# Sheet1.net
KiCad netlist of a schematic drawn in EasyEDA Pro
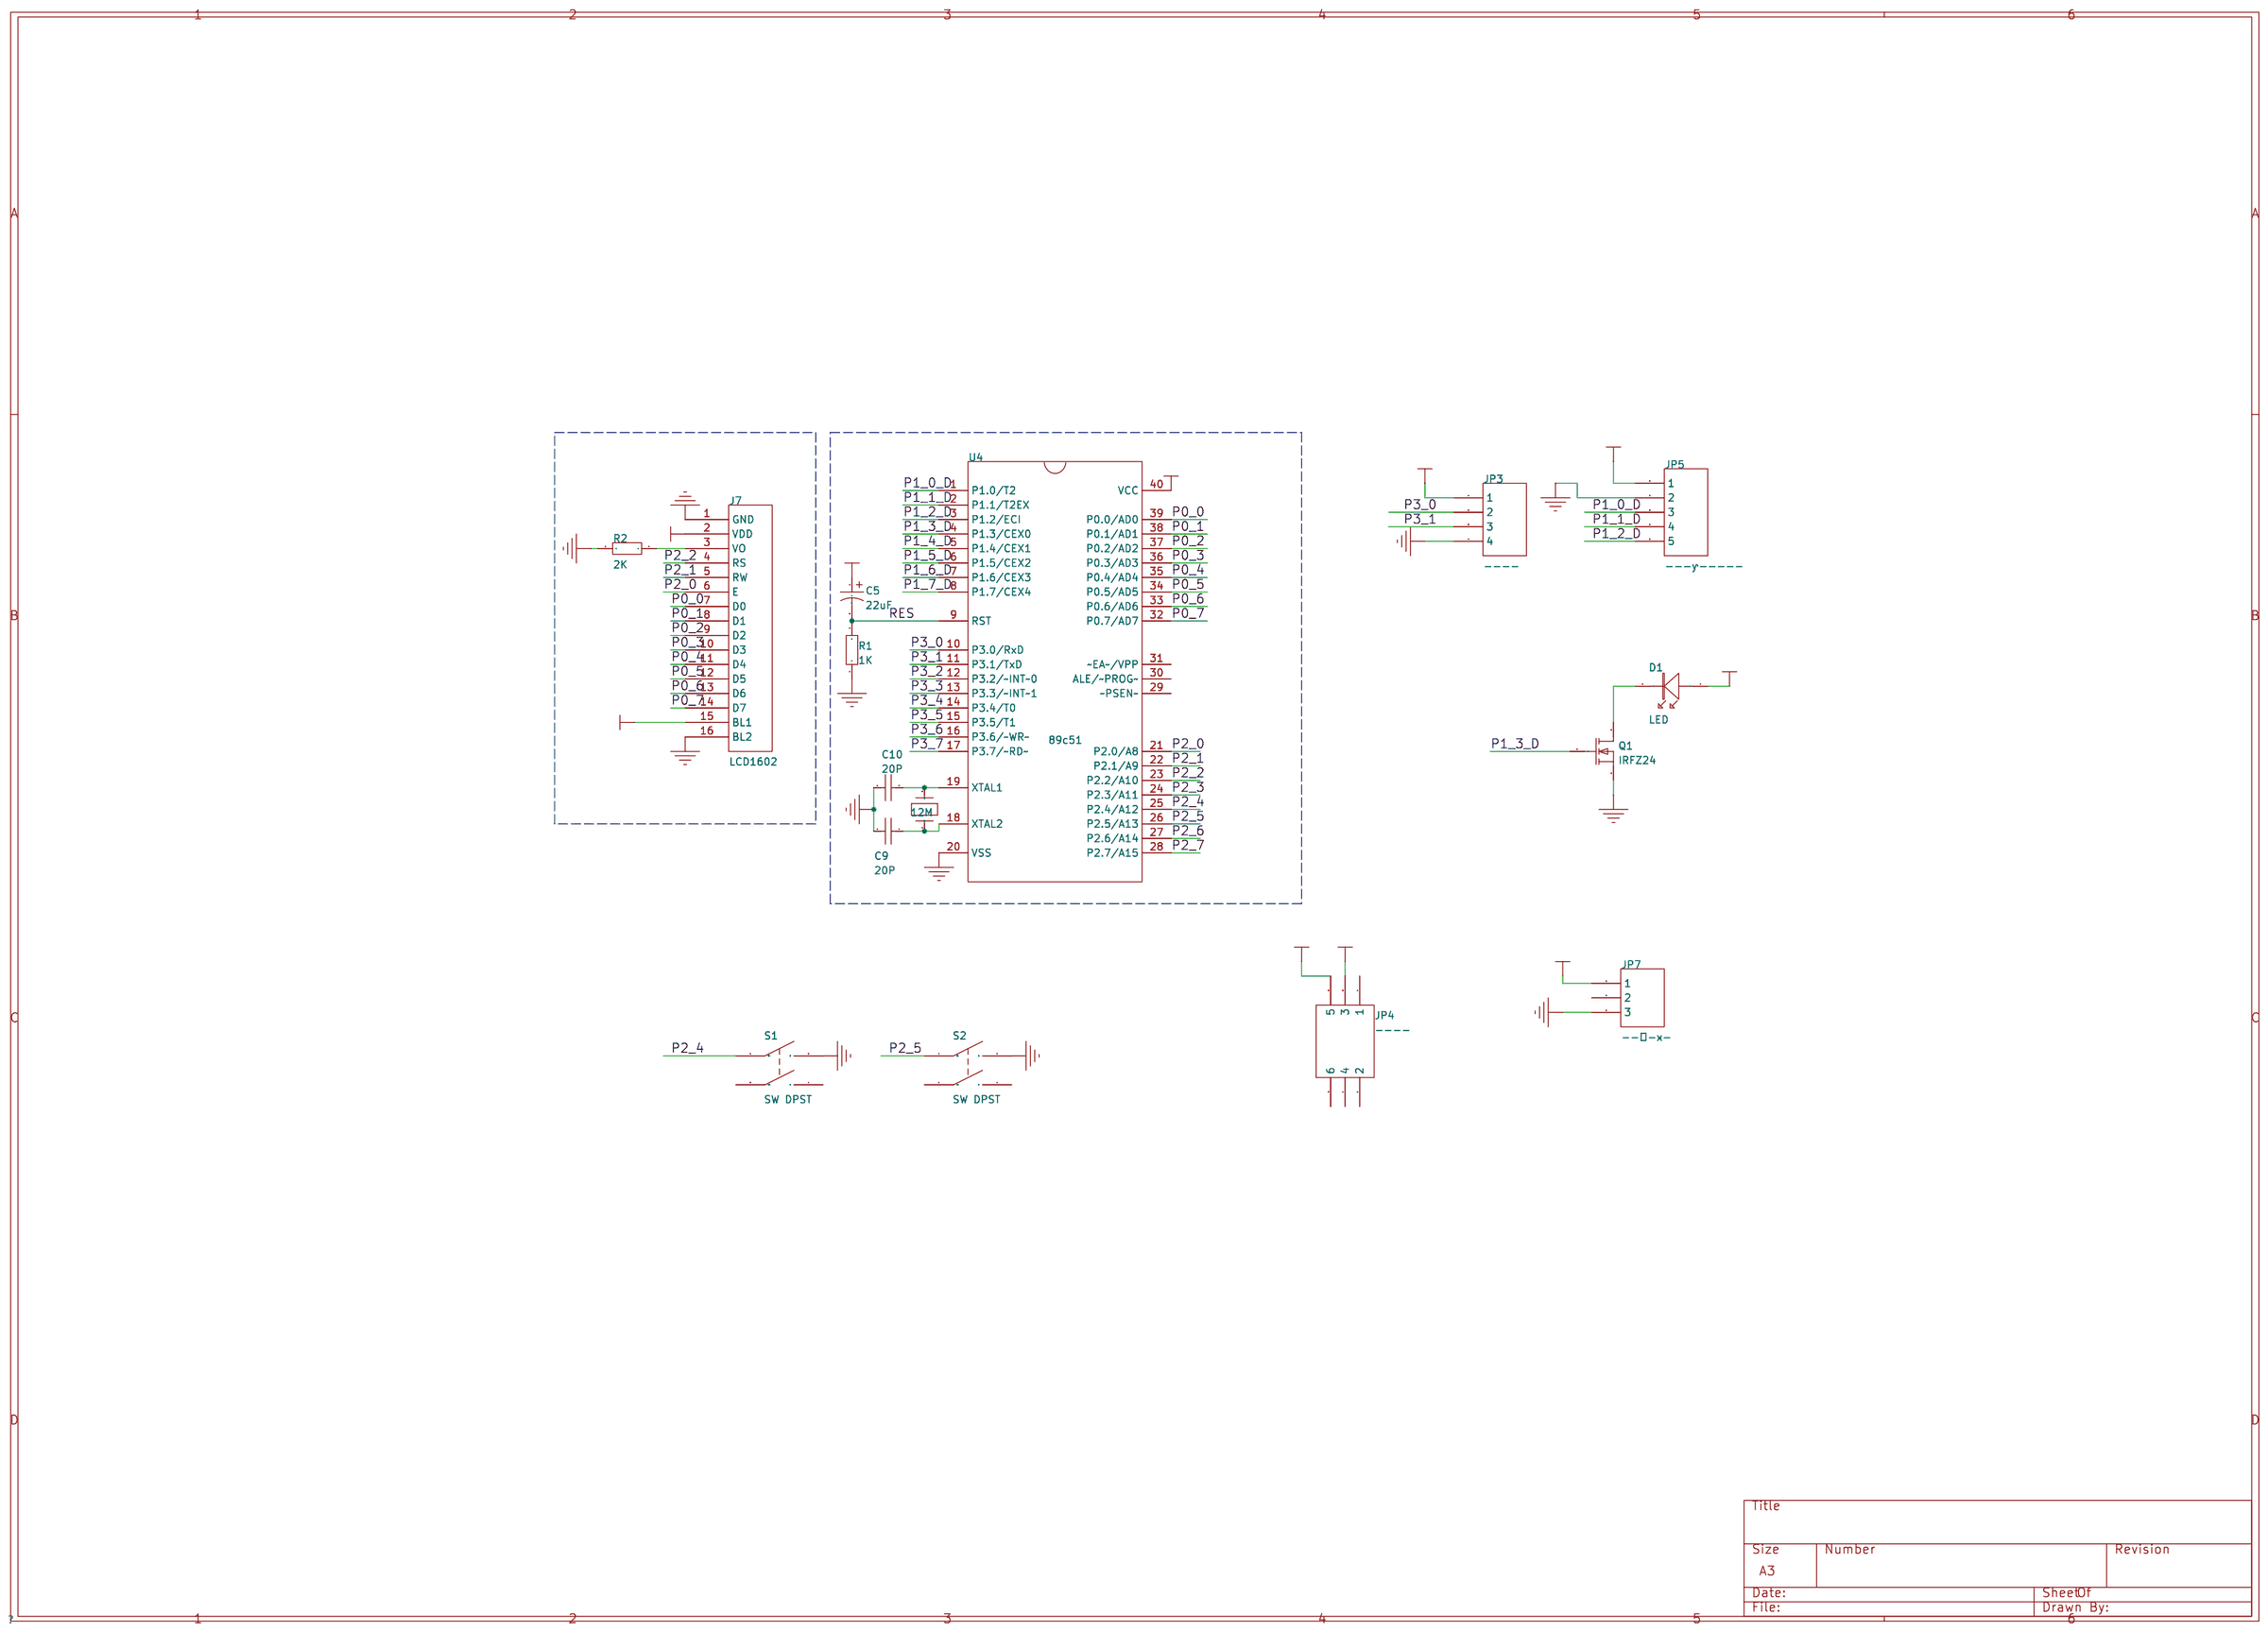
[diagram p0: schematic sheet]

(export (version "E")
  (design (tool "Eeschema 10.0.6"))
  (components
    (comp (ref "C5")
      (value "22uF")
      (description "Polarized Capacitor (Radial)")
      (fields (field (name "Publisher") "Altium Limited"))
      (libsource (lib "easyedapro") (part "Cap Pol1"))
    )
    (comp (ref "C9") (value "20P") (description "Capacitor") (libsource (lib "easyedapro") (part "CAP")))
    (comp (ref "C10") (value "20P") (description "Capacitor") (libsource (lib "easyedapro") (part "CAP")))
    (comp (ref "D1") (value "LED") (libsource (lib "easyedapro") (part "LED")))
    (comp (ref "J7") (value "LCD1602") (libsource (lib "easyedapro") (part "LCD1602")))
    (comp (ref "JP3")
      (value "----")
      (description "4 Pin Header")
      (libsource (lib "easyedapro") (part "4 HEADER"))
    )
    (comp (ref "JP4") (value "----") (libsource (lib "easyedapro") (part "HEADER 3X2")))
    (comp (ref "JP5") (value "---ƴ-----") (libsource (lib "easyedapro") (part "HEADER 5")))
    (comp (ref "JP7") (value "--Դ-ӿ-") (libsource (lib "easyedapro") (part "HEADER 3")))
    (comp (ref "Q1")
      (value "IRFZ24")
      (description "N-Channel MOSFET")
      (libsource (lib "easyedapro") (part "IRFZ24"))
    )
    (comp (ref "R1")
      (value "1K")
      (description "Resistor")
      (fields (field (name "Publisher") "Altium Limited"))
      (libsource (lib "easyedapro") (part "Res2"))
    )
    (comp (ref "R2")
      (value "2K")
      (description "Resistor")
      (fields (field (name "Publisher") "Altium Limited"))
      (libsource (lib "easyedapro") (part "Res2"))
    )
    (comp (ref "S1") (value "SW DPST") (libsource (lib "easyedapro") (part "SW DPST")))
    (comp (ref "S2") (value "SW DPST") (libsource (lib "easyedapro") (part "SW DPST")))
    (comp (ref "U4") (value "89c51") (libsource (lib "easyedapro") (part "89c51")))
    (comp (ref "Y4") (value "12M") (description "Crystal") (libsource (lib "easyedapro") (part "CRYSTAL")))
  )
  (nets
    (net (code "1") (name "/P0_0") (class "Default")
      (node (ref "J7") (pin "7") (pinfunction "D0_7") (pintype "unspecified"))
      (node (ref "U4") (pin "39") (pinfunction "P0.0/AD0_39") (pintype "bidirectional"))
    )
    (net (code "2") (name "/P0_1") (class "Default")
      (node (ref "J7") (pin "8") (pinfunction "D1_8") (pintype "unspecified"))
      (node (ref "U4") (pin "38") (pinfunction "P0.1/AD1_38") (pintype "bidirectional"))
    )
    (net (code "3") (name "/P0_2") (class "Default")
      (node (ref "J7") (pin "9") (pinfunction "D2_9") (pintype "unspecified"))
      (node (ref "U4") (pin "37") (pinfunction "P0.2/AD2_37") (pintype "bidirectional"))
    )
    (net (code "4") (name "/P0_3") (class "Default")
      (node (ref "J7") (pin "10") (pinfunction "D3_10") (pintype "unspecified"))
      (node (ref "U4") (pin "36") (pinfunction "P0.3/AD3_36") (pintype "bidirectional"))
    )
    (net (code "5") (name "/P0_4") (class "Default")
      (node (ref "J7") (pin "11") (pinfunction "D4_11") (pintype "unspecified"))
      (node (ref "U4") (pin "35") (pinfunction "P0.4/AD4_35") (pintype "bidirectional"))
    )
    (net (code "6") (name "/P0_5") (class "Default")
      (node (ref "J7") (pin "12") (pinfunction "D5_12") (pintype "unspecified"))
      (node (ref "U4") (pin "34") (pinfunction "P0.5/AD5_34") (pintype "bidirectional"))
    )
    (net (code "7") (name "/P0_6") (class "Default")
      (node (ref "J7") (pin "13") (pinfunction "D6_13") (pintype "unspecified"))
      (node (ref "U4") (pin "33") (pinfunction "P0.6/AD6_33") (pintype "bidirectional"))
    )
    (net (code "8") (name "/P0_7") (class "Default")
      (node (ref "J7") (pin "14") (pinfunction "D7_14") (pintype "unspecified"))
      (node (ref "U4") (pin "32") (pinfunction "P0.7/AD7_32") (pintype "bidirectional"))
    )
    (net (code "9") (name "/P1_0_D") (class "Default")
      (node (ref "JP5") (pin "3") (pinfunction "3_3") (pintype "unspecified"))
      (node (ref "U4") (pin "1") (pinfunction "P1.0/T2_1") (pintype "bidirectional"))
    )
    (net (code "10") (name "/P1_1_D") (class "Default")
      (node (ref "JP5") (pin "4") (pinfunction "4_4") (pintype "unspecified"))
      (node (ref "U4") (pin "2") (pinfunction "P1.1/T2EX_2") (pintype "bidirectional"))
    )
    (net (code "11") (name "/P1_2_D") (class "Default")
      (node (ref "JP5") (pin "5") (pinfunction "5_5") (pintype "unspecified"))
      (node (ref "U4") (pin "3") (pinfunction "P1.2/ECI_3") (pintype "bidirectional"))
    )
    (net (code "12") (name "/P1_3_D") (class "Default")
      (node (ref "Q1") (pin "1") (pinfunction "G_1") (pintype "input"))
      (node (ref "U4") (pin "4") (pinfunction "P1.3/CEX0_4") (pintype "bidirectional"))
    )
    (net (code "13") (name "/P1_4_D") (class "Default")
      (node (ref "U4") (pin "5") (pinfunction "P1.4/CEX1_5") (pintype "bidirectional"))
    )
    (net (code "14") (name "/P1_5_D") (class "Default")
      (node (ref "U4") (pin "6") (pinfunction "P1.5/CEX2_6") (pintype "bidirectional"))
    )
    (net (code "15") (name "/P1_6_D") (class "Default")
      (node (ref "U4") (pin "7") (pinfunction "P1.6/CEX3_7") (pintype "bidirectional"))
    )
    (net (code "16") (name "/P1_7_D") (class "Default")
      (node (ref "U4") (pin "8") (pinfunction "P1.7/CEX4_8") (pintype "bidirectional"))
    )
    (net (code "17") (name "/P2_0") (class "Default")
      (node (ref "J7") (pin "6") (pinfunction "E_6") (pintype "unspecified"))
      (node (ref "U4") (pin "21") (pinfunction "P2.0/A8_21") (pintype "bidirectional"))
    )
    (net (code "18") (name "/P2_1") (class "Default")
      (node (ref "J7") (pin "5") (pinfunction "RW_5") (pintype "unspecified"))
      (node (ref "U4") (pin "22") (pinfunction "P2.1/A9_22") (pintype "bidirectional"))
    )
    (net (code "19") (name "/P2_2") (class "Default")
      (node (ref "J7") (pin "4") (pinfunction "RS_4") (pintype "unspecified"))
      (node (ref "U4") (pin "23") (pinfunction "P2.2/A10_23") (pintype "bidirectional"))
    )
    (net (code "20") (name "/P2_3") (class "Default")
      (node (ref "U4") (pin "24") (pinfunction "P2.3/A11_24") (pintype "bidirectional"))
    )
    (net (code "21") (name "/P2_4") (class "Default")
      (node (ref "S1") (pin "1") (pinfunction "COMMON1_1") (pintype "unspecified"))
      (node (ref "U4") (pin "25") (pinfunction "P2.4/A12_25") (pintype "bidirectional"))
    )
    (net (code "22") (name "/P2_5") (class "Default")
      (node (ref "S2") (pin "1") (pinfunction "COMMON1_1") (pintype "unspecified"))
      (node (ref "U4") (pin "26") (pinfunction "P2.5/A13_26") (pintype "bidirectional"))
    )
    (net (code "23") (name "/P2_6") (class "Default")
      (node (ref "U4") (pin "27") (pinfunction "P2.6/A14_27") (pintype "bidirectional"))
    )
    (net (code "24") (name "/P2_7") (class "Default")
      (node (ref "U4") (pin "28") (pinfunction "P2.7/A15_28") (pintype "bidirectional"))
    )
    (net (code "25") (name "/P3_0") (class "Default")
      (node (ref "JP3") (pin "2") (pinfunction "2_2") (pintype "unspecified"))
      (node (ref "U4") (pin "10") (pinfunction "P3.0/RxD_10") (pintype "bidirectional"))
    )
    (net (code "26") (name "/P3_1") (class "Default")
      (node (ref "JP3") (pin "3") (pinfunction "3_3") (pintype "unspecified"))
      (node (ref "U4") (pin "11") (pinfunction "P3.1/TxD_11") (pintype "bidirectional"))
    )
    (net (code "27") (name "/P3_2") (class "Default")
      (node (ref "U4") (pin "12") (pinfunction "P3.2/~INT~0_12") (pintype "bidirectional"))
    )
    (net (code "28") (name "/P3_3") (class "Default")
      (node (ref "U4") (pin "13") (pinfunction "P3.3/~INT~1_13") (pintype "bidirectional"))
    )
    (net (code "29") (name "/P3_4") (class "Default")
      (node (ref "U4") (pin "14") (pinfunction "P3.4/T0_14") (pintype "bidirectional"))
    )
    (net (code "30") (name "/P3_5") (class "Default")
      (node (ref "U4") (pin "15") (pinfunction "P3.5/T1_15") (pintype "bidirectional"))
    )
    (net (code "31") (name "/P3_6") (class "Default")
      (node (ref "U4") (pin "16") (pinfunction "P3.6/~WR~_16") (pintype "bidirectional"))
    )
    (net (code "32") (name "/P3_7") (class "Default")
      (node (ref "U4") (pin "17") (pinfunction "P3.7/~RD~_17") (pintype "bidirectional"))
    )
    (net (code "33") (name "/RES") (class "Default")
      (node (ref "C5") (pin "2") (pinfunction "2_2") (pintype "unspecified"))
      (node (ref "R1") (pin "2") (pinfunction "2_2") (pintype "unspecified"))
      (node (ref "U4") (pin "9") (pinfunction "RST_9") (pintype "input"))
    )
    (net (code "34") (name "GND") (class "Default")
      (node (ref "C10") (pin "1") (pinfunction "1_1") (pintype "unspecified"))
      (node (ref "C9") (pin "2") (pinfunction "2_2") (pintype "unspecified"))
      (node (ref "J7") (pin "1") (pinfunction "GND_1") (pintype "unspecified"))
      (node (ref "J7") (pin "16") (pinfunction "BL2_16") (pintype "unspecified"))
      (node (ref "JP3") (pin "4") (pinfunction "4_4") (pintype "unspecified"))
      (node (ref "JP5") (pin "2") (pinfunction "2_2") (pintype "unspecified"))
      (node (ref "JP7") (pin "3") (pinfunction "3_3") (pintype "unspecified"))
      (node (ref "Q1") (pin "3") (pinfunction "S_3") (pintype "input"))
      (node (ref "R1") (pin "1") (pinfunction "1_1") (pintype "unspecified"))
      (node (ref "R2") (pin "2") (pinfunction "2_2") (pintype "unspecified"))
      (node (ref "S1") (pin "2") (pinfunction "NO1_2") (pintype "unspecified"))
      (node (ref "S2") (pin "2") (pinfunction "NO1_2") (pintype "unspecified"))
      (node (ref "U4") (pin "20") (pinfunction "VSS_20") (pintype "unspecified"))
    )
    (net (code "35") (name "Net-(J7-VO)") (class "Default")
      (node (ref "J7") (pin "3") (pinfunction "VO_3") (pintype "unspecified"))
      (node (ref "R2") (pin "1") (pinfunction "1_1") (pintype "unspecified"))
    )
    (net (code "36") (name "Net-(Q1-D)") (class "Default")
      (node (ref "D1") (pin "2") (pinfunction "2_2") (pintype "unspecified"))
      (node (ref "Q1") (pin "2") (pinfunction "D_2") (pintype "input"))
    )
    (net (code "37") (name "Net-(U4-XTAL1)") (class "Default")
      (node (ref "C10") (pin "2") (pinfunction "2_2") (pintype "unspecified"))
      (node (ref "U4") (pin "19") (pinfunction "XTAL1_19") (pintype "input"))
      (node (ref "Y4") (pin "2") (pinfunction "2_2") (pintype "unspecified"))
    )
    (net (code "38") (name "Net-(U4-XTAL2)") (class "Default")
      (node (ref "C9") (pin "1") (pinfunction "1_1") (pintype "unspecified"))
      (node (ref "U4") (pin "18") (pinfunction "XTAL2_18") (pintype "output"))
      (node (ref "Y4") (pin "1") (pinfunction "1_1") (pintype "unspecified"))
    )
    (net (code "39") (name "VCC") (class "Default")
      (node (ref "C5") (pin "1") (pinfunction "1_1") (pintype "unspecified"))
      (node (ref "D1") (pin "1") (pinfunction "1_1") (pintype "unspecified"))
      (node (ref "J7") (pin "15") (pinfunction "BL1_15") (pintype "unspecified"))
      (node (ref "J7") (pin "2") (pinfunction "VDD_2") (pintype "unspecified"))
      (node (ref "JP3") (pin "1") (pinfunction "1_1") (pintype "unspecified"))
      (node (ref "JP4") (pin "3") (pinfunction "3_3") (pintype "unspecified"))
      (node (ref "JP5") (pin "1") (pinfunction "1_1") (pintype "unspecified"))
      (node (ref "U4") (pin "40") (pinfunction "VCC_40") (pintype "unspecified"))
    )
    (net (code "40") (name "VIN") (class "Default")
      (node (ref "JP4") (pin "5") (pinfunction "5_5") (pintype "unspecified"))
      (node (ref "JP7") (pin "1") (pinfunction "1_1") (pintype "unspecified"))
    )
    (net (code "41") (name "unconnected-(JP4-Pad1)") (class "Default")
      (node (ref "JP4") (pin "1") (pinfunction "1_1") (pintype "unspecified"))
    )
    (net (code "42") (name "unconnected-(JP4-Pad2)") (class "Default")
      (node (ref "JP4") (pin "2") (pinfunction "2_2") (pintype "unspecified"))
    )
    (net (code "43") (name "unconnected-(JP4-Pad4)") (class "Default")
      (node (ref "JP4") (pin "4") (pinfunction "4_4") (pintype "unspecified"))
    )
    (net (code "44") (name "unconnected-(JP4-Pad6)") (class "Default")
      (node (ref "JP4") (pin "6") (pinfunction "6_6") (pintype "unspecified"))
    )
    (net (code "45") (name "unconnected-(JP7-Pad2)") (class "Default")
      (node (ref "JP7") (pin "2") (pinfunction "2_2") (pintype "unspecified"))
    )
    (net (code "46") (name "unconnected-(S1-COMMON2-Pad3)") (class "Default")
      (node (ref "S1") (pin "3") (pinfunction "COMMON2_3") (pintype "unspecified"))
    )
    (net (code "47") (name "unconnected-(S1-NO2-Pad4)") (class "Default")
      (node (ref "S1") (pin "4") (pinfunction "NO2_4") (pintype "unspecified"))
    )
    (net (code "48") (name "unconnected-(S2-COMMON2-Pad3)") (class "Default")
      (node (ref "S2") (pin "3") (pinfunction "COMMON2_3") (pintype "unspecified"))
    )
    (net (code "49") (name "unconnected-(S2-NO2-Pad4)") (class "Default")
      (node (ref "S2") (pin "4") (pinfunction "NO2_4") (pintype "unspecified"))
    )
    (net (code "50") (name "unconnected-(U4-ALE{slash}~PROG~-Pad30)") (class "Default")
      (node (ref "U4") (pin "30") (pinfunction "ALE/~PROG~_30") (pintype "bidirectional"))
    )
    (net (code "51") (name "unconnected-(U4-~EA~{slash}VPP-Pad31)") (class "Default")
      (node (ref "U4") (pin "31") (pinfunction "~EA~/VPP_31") (pintype "input"))
    )
    (net (code "52") (name "unconnected-(U4-~PSEN~-Pad29)") (class "Default")
      (node (ref "U4") (pin "29") (pinfunction "~PSEN~_29") (pintype "output"))
    )
  )
)
